# OnePhaseMain.net
KiCad netlist of a schematic drawn in Altium Designer
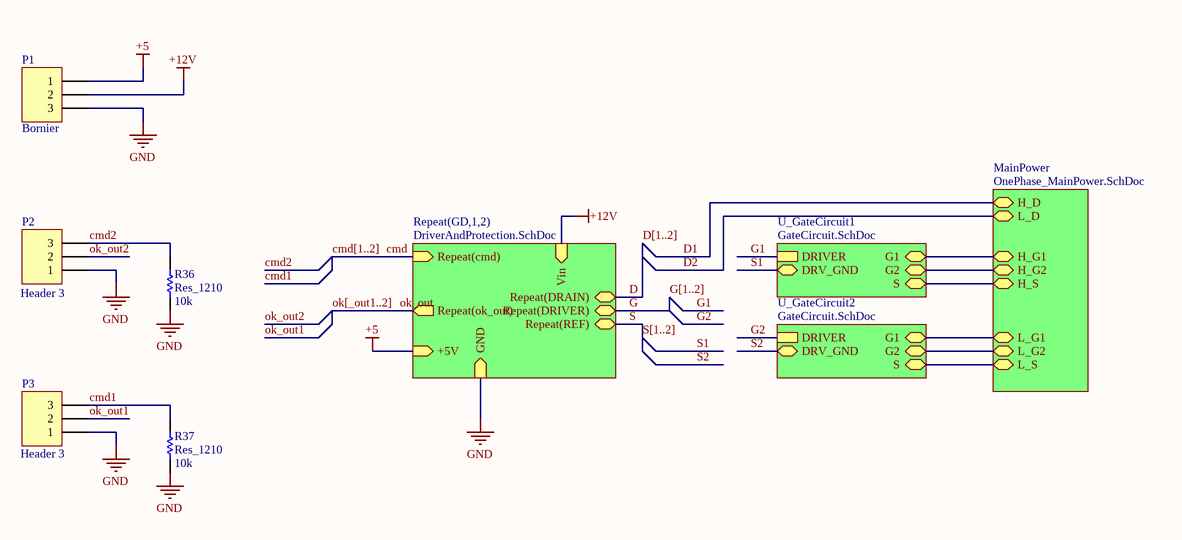
[diagram p0: OnePhaseMain.SchDoc]

(export (version "E")
  (design (tool "Eeschema 10.0.6"))
  (components
    (comp (ref "P1")
      (value "Bornier")
      (footprint "3 Pin  Borner")
      (description "Header, 3-Pin")
      (libsource (lib "") (part "Header 3_1"))
    )
    (comp (ref "P2")
      (value "Header 3")
      (footprint "HDR1X3")
      (description "Header, 3-Pin")
      (libsource (lib "Miscellaneous Connectors") (part "Header 3"))
    )
    (comp (ref "P3")
      (value "Header 3")
      (footprint "HDR1X3")
      (description "Header, 3-Pin")
      (libsource (lib "Miscellaneous Connectors") (part "Header 3"))
    )
    (comp (ref "R36")
      (value "Res_1210")
      (footprint "0805_W")
      (description "Resistor")
      (fields (field (name "ALTIUM_VALUE") "10k"))
      (libsource (lib "Inversor_LCEE") (part "Res_0805"))
    )
    (comp (ref "R37")
      (value "Res_1210")
      (footprint "0805_W")
      (description "Resistor")
      (fields (field (name "ALTIUM_VALUE") "10k"))
      (libsource (lib "Inversor_LCEE") (part "Res_0805"))
    )
  )
  (nets
    (net (code "2") (name "+5") (class "Default")
      (node (ref "P1") (pin "1") (pinfunction "1_1") (pintype "passive"))
    )
    (net (code "3") (name "+12V") (class "Default")
      (node (ref "P1") (pin "2") (pinfunction "2_2") (pintype "passive"))
    )
    (net (code "23") (name "/cmd1") (class "Default")
      (node (ref "P3") (pin "3") (pinfunction "3_3") (pintype "passive"))
      (node (ref "R37") (pin "1") (pinfunction "1_1") (pintype "passive"))
    )
    (net (code "24") (name "/cmd2") (class "Default")
      (node (ref "P2") (pin "3") (pinfunction "3_3") (pintype "passive"))
      (node (ref "R36") (pin "1") (pinfunction "1_1") (pintype "passive"))
    )
    (net (code "27") (name "/ok_out1") (class "Default")
      (node (ref "P3") (pin "2") (pinfunction "2_2") (pintype "passive"))
    )
    (net (code "28") (name "/ok_out2") (class "Default")
      (node (ref "P2") (pin "2") (pinfunction "2_2") (pintype "passive"))
    )
    (net (code "30") (name "GND") (class "Default")
      (node (ref "P1") (pin "3") (pinfunction "3_3") (pintype "passive"))
      (node (ref "P2") (pin "1") (pinfunction "1_1") (pintype "passive"))
      (node (ref "P3") (pin "1") (pinfunction "1_1") (pintype "passive"))
      (node (ref "R36") (pin "2") (pinfunction "2_2") (pintype "passive"))
      (node (ref "R37") (pin "2") (pinfunction "2_2") (pintype "passive"))
    )
  )
)
